# line_sensor.net
KiCad netlist of a schematic drawn in EAGLE
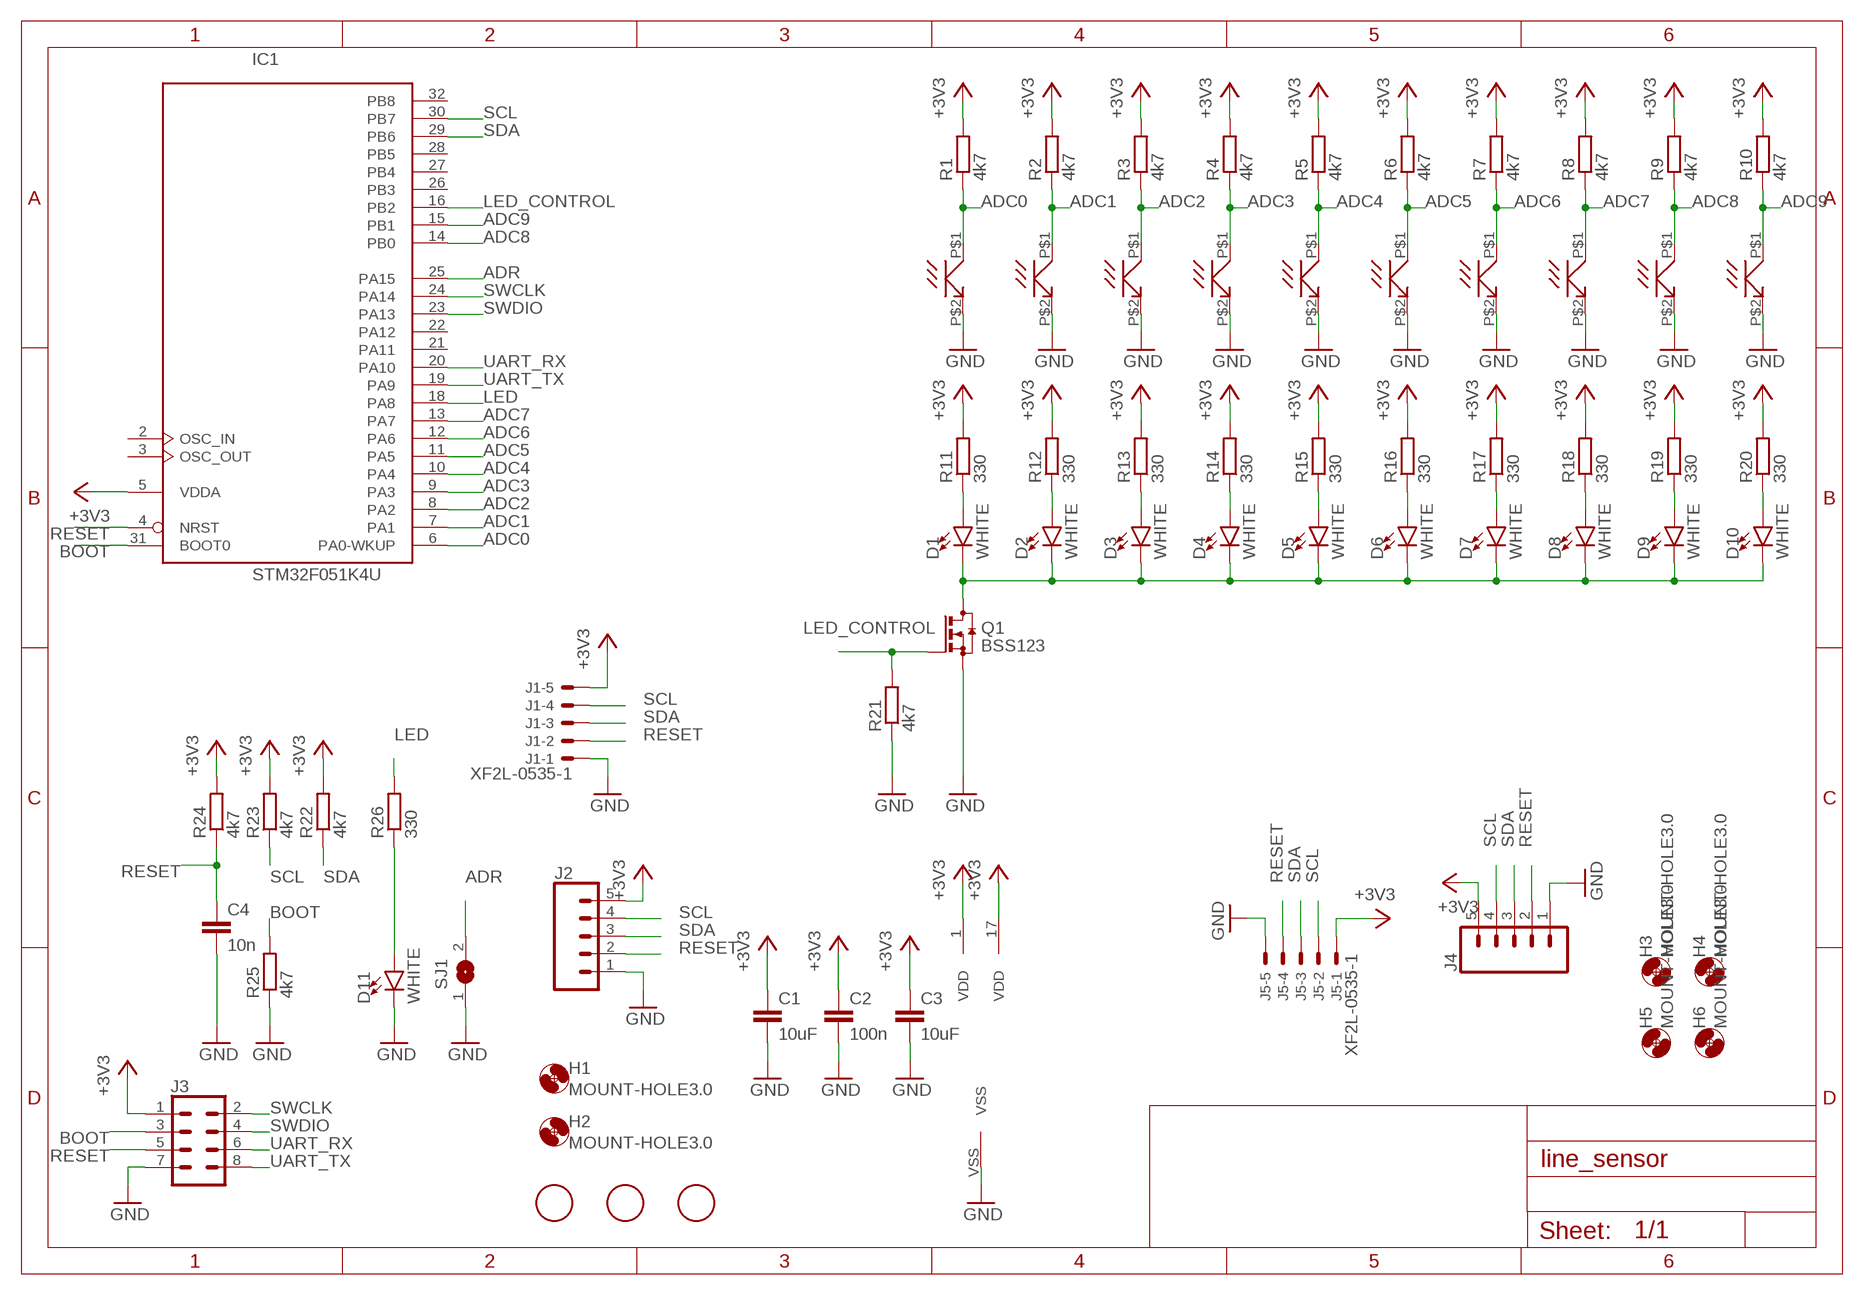
[diagram p0: schematic, sheet 1]

(export (version "E")
  (design (tool "Eeschema 10.0.6"))
  (components
    (comp (ref "C1")
      (value "10uF")
      (footprint "eagle-import:C0805K")
      (libsource (lib "eagle-import") (part "C-EUC0805K"))
    )
    (comp (ref "C2")
      (value "100n")
      (footprint "eagle-import:C0805K")
      (libsource (lib "eagle-import") (part "C-EUC0805K"))
    )
    (comp (ref "C3")
      (value "10uF")
      (footprint "eagle-import:C0805K")
      (libsource (lib "eagle-import") (part "C-EUC0805K"))
    )
    (comp (ref "C4")
      (value "10n")
      (footprint "eagle-import:C0805K")
      (libsource (lib "eagle-import") (part "C-EUC0805K"))
    )
    (comp (ref "D1")
      (value "WHITE")
      (footprint "eagle-import:LED-1206")
      (libsource (lib "eagle-import") (part "LED-WHITE1206"))
    )
    (comp (ref "D2")
      (value "WHITE")
      (footprint "eagle-import:LED-1206")
      (libsource (lib "eagle-import") (part "LED-WHITE1206"))
    )
    (comp (ref "D3")
      (value "WHITE")
      (footprint "eagle-import:LED-1206")
      (libsource (lib "eagle-import") (part "LED-WHITE1206"))
    )
    (comp (ref "D4")
      (value "WHITE")
      (footprint "eagle-import:LED-1206")
      (libsource (lib "eagle-import") (part "LED-WHITE1206"))
    )
    (comp (ref "D5")
      (value "WHITE")
      (footprint "eagle-import:LED-1206")
      (libsource (lib "eagle-import") (part "LED-WHITE1206"))
    )
    (comp (ref "D6")
      (value "WHITE")
      (footprint "eagle-import:LED-1206")
      (libsource (lib "eagle-import") (part "LED-WHITE1206"))
    )
    (comp (ref "D7")
      (value "WHITE")
      (footprint "eagle-import:LED-1206")
      (libsource (lib "eagle-import") (part "LED-WHITE1206"))
    )
    (comp (ref "D8")
      (value "WHITE")
      (footprint "eagle-import:LED-1206")
      (libsource (lib "eagle-import") (part "LED-WHITE1206"))
    )
    (comp (ref "D9")
      (value "WHITE")
      (footprint "eagle-import:LED-1206")
      (libsource (lib "eagle-import") (part "LED-WHITE1206"))
    )
    (comp (ref "D10")
      (value "WHITE")
      (footprint "eagle-import:LED-1206")
      (libsource (lib "eagle-import") (part "LED-WHITE1206"))
    )
    (comp (ref "D11")
      (value "WHITE")
      (footprint "eagle-import:LED-1206")
      (libsource (lib "eagle-import") (part "LED-WHITE1206"))
    )
    (comp (ref "H1")
      (value "MOUNT-HOLE3.0")
      (footprint "eagle-import:3,0")
      (libsource (lib "eagle-import") (part "MOUNT-HOLE3.0"))
    )
    (comp (ref "H2")
      (value "MOUNT-HOLE3.0")
      (footprint "eagle-import:3,0")
      (libsource (lib "eagle-import") (part "MOUNT-HOLE3.0"))
    )
    (comp (ref "H3")
      (value "MOUNT-HOLE3.0")
      (footprint "eagle-import:3,0")
      (libsource (lib "eagle-import") (part "MOUNT-HOLE3.0"))
    )
    (comp (ref "H4")
      (value "MOUNT-HOLE3.0")
      (footprint "eagle-import:3,0")
      (libsource (lib "eagle-import") (part "MOUNT-HOLE3.0"))
    )
    (comp (ref "H5")
      (value "MOUNT-HOLE3.0")
      (footprint "eagle-import:3,0")
      (libsource (lib "eagle-import") (part "MOUNT-HOLE3.0"))
    )
    (comp (ref "H6")
      (value "MOUNT-HOLE3.0")
      (footprint "eagle-import:3,0")
      (libsource (lib "eagle-import") (part "MOUNT-HOLE3.0"))
    )
    (comp (ref "IC1")
      (value "STM32F051K4U")
      (footprint "eagle-import:UFQFPN32")
      (libsource (lib "eagle-import") (part "STM32F051KU4"))
    )
    (comp (ref "J1")
      (value "XF2L-0535-1")
      (footprint "eagle-import:XF2L-0535-1")
      (fields (field (name "MPN") "XF2L-0535-1A"))
      (libsource (lib "eagle-import") (part "XF2-05?35-1L"))
    )
    (comp (ref "J2")
      (value "CONN_05")
      (footprint "eagle-import:1X05")
      (libsource (lib "eagle-import") (part "CONN_05"))
    )
    (comp (ref "J3")
      (value "CONN_04X2")
      (footprint "eagle-import:2X4")
      (libsource (lib "eagle-import") (part "CONN_04X2"))
    )
    (comp (ref "J4")
      (value "CONN_05")
      (footprint "eagle-import:1X05")
      (libsource (lib "eagle-import") (part "CONN_05"))
    )
    (comp (ref "J5")
      (value "XF2L-0535-1")
      (footprint "eagle-import:XF2L-0535-1")
      (fields (field (name "MPN") "XF2L-0535-1A"))
      (libsource (lib "eagle-import") (part "XF2-05?35-1L"))
    )
    (comp (ref "Q1")
      (value "BSS123")
      (footprint "eagle-import:SOT23")
      (libsource (lib "eagle-import") (part "BSS123"))
    )
    (comp (ref "R1")
      (value "4k7")
      (footprint "eagle-import:M0805")
      (libsource (lib "eagle-import") (part "R-EU_M0805"))
    )
    (comp (ref "R2")
      (value "4k7")
      (footprint "eagle-import:M0805")
      (libsource (lib "eagle-import") (part "R-EU_M0805"))
    )
    (comp (ref "R3")
      (value "4k7")
      (footprint "eagle-import:M0805")
      (libsource (lib "eagle-import") (part "R-EU_M0805"))
    )
    (comp (ref "R4")
      (value "4k7")
      (footprint "eagle-import:M0805")
      (libsource (lib "eagle-import") (part "R-EU_M0805"))
    )
    (comp (ref "R5")
      (value "4k7")
      (footprint "eagle-import:M0805")
      (libsource (lib "eagle-import") (part "R-EU_M0805"))
    )
    (comp (ref "R6")
      (value "4k7")
      (footprint "eagle-import:M0805")
      (libsource (lib "eagle-import") (part "R-EU_M0805"))
    )
    (comp (ref "R7")
      (value "4k7")
      (footprint "eagle-import:M0805")
      (libsource (lib "eagle-import") (part "R-EU_M0805"))
    )
    (comp (ref "R8")
      (value "4k7")
      (footprint "eagle-import:M0805")
      (libsource (lib "eagle-import") (part "R-EU_M0805"))
    )
    (comp (ref "R9")
      (value "4k7")
      (footprint "eagle-import:M0805")
      (libsource (lib "eagle-import") (part "R-EU_M0805"))
    )
    (comp (ref "R10")
      (value "4k7")
      (footprint "eagle-import:M0805")
      (libsource (lib "eagle-import") (part "R-EU_M0805"))
    )
    (comp (ref "R11")
      (value "330")
      (footprint "eagle-import:M0805")
      (libsource (lib "eagle-import") (part "R-EU_M0805"))
    )
    (comp (ref "R12")
      (value "330")
      (footprint "eagle-import:M0805")
      (libsource (lib "eagle-import") (part "R-EU_M0805"))
    )
    (comp (ref "R13")
      (value "330")
      (footprint "eagle-import:M0805")
      (libsource (lib "eagle-import") (part "R-EU_M0805"))
    )
    (comp (ref "R14")
      (value "330")
      (footprint "eagle-import:M0805")
      (libsource (lib "eagle-import") (part "R-EU_M0805"))
    )
    (comp (ref "R15")
      (value "330")
      (footprint "eagle-import:M0805")
      (libsource (lib "eagle-import") (part "R-EU_M0805"))
    )
    (comp (ref "R16")
      (value "330")
      (footprint "eagle-import:M0805")
      (libsource (lib "eagle-import") (part "R-EU_M0805"))
    )
    (comp (ref "R17")
      (value "330")
      (footprint "eagle-import:M0805")
      (libsource (lib "eagle-import") (part "R-EU_M0805"))
    )
    (comp (ref "R18")
      (value "330")
      (footprint "eagle-import:M0805")
      (libsource (lib "eagle-import") (part "R-EU_M0805"))
    )
    (comp (ref "R19")
      (value "330")
      (footprint "eagle-import:M0805")
      (libsource (lib "eagle-import") (part "R-EU_M0805"))
    )
    (comp (ref "R20")
      (value "330")
      (footprint "eagle-import:M0805")
      (libsource (lib "eagle-import") (part "R-EU_M0805"))
    )
    (comp (ref "R21")
      (value "4k7")
      (footprint "eagle-import:M0805")
      (libsource (lib "eagle-import") (part "R-EU_M0805"))
    )
    (comp (ref "R22")
      (value "4k7")
      (footprint "eagle-import:M0805")
      (libsource (lib "eagle-import") (part "R-EU_M0805"))
    )
    (comp (ref "R23")
      (value "4k7")
      (footprint "eagle-import:M0805")
      (libsource (lib "eagle-import") (part "R-EU_M0805"))
    )
    (comp (ref "R24")
      (value "4k7")
      (footprint "eagle-import:M0805")
      (libsource (lib "eagle-import") (part "R-EU_M0805"))
    )
    (comp (ref "R25")
      (value "4k7")
      (footprint "eagle-import:M0805")
      (libsource (lib "eagle-import") (part "R-EU_M0805"))
    )
    (comp (ref "R26")
      (value "330")
      (footprint "eagle-import:M0805")
      (libsource (lib "eagle-import") (part "R-EU_M0805"))
    )
    (comp (ref "SJ1") (value "SJ") (footprint "eagle-import:SJ") (libsource (lib "eagle-import") (part "SJ")))
    (comp (ref "U$1")
      (value "SFH3710")
      (footprint "eagle-import:SFH710")
      (libsource (lib "eagle-import") (part "SFH3710"))
    )
    (comp (ref "U$2")
      (value "SFH3710")
      (footprint "eagle-import:SFH710")
      (libsource (lib "eagle-import") (part "SFH3710"))
    )
    (comp (ref "U$3")
      (value "SFH3710")
      (footprint "eagle-import:SFH710")
      (libsource (lib "eagle-import") (part "SFH3710"))
    )
    (comp (ref "U$4")
      (value "SFH3710")
      (footprint "eagle-import:SFH710")
      (libsource (lib "eagle-import") (part "SFH3710"))
    )
    (comp (ref "U$5")
      (value "SFH3710")
      (footprint "eagle-import:SFH710")
      (libsource (lib "eagle-import") (part "SFH3710"))
    )
    (comp (ref "U$6")
      (value "SFH3710")
      (footprint "eagle-import:SFH710")
      (libsource (lib "eagle-import") (part "SFH3710"))
    )
    (comp (ref "U$7")
      (value "SFH3710")
      (footprint "eagle-import:SFH710")
      (libsource (lib "eagle-import") (part "SFH3710"))
    )
    (comp (ref "U$8")
      (value "SFH3710")
      (footprint "eagle-import:SFH710")
      (libsource (lib "eagle-import") (part "SFH3710"))
    )
    (comp (ref "U$9")
      (value "SFH3710")
      (footprint "eagle-import:SFH710")
      (libsource (lib "eagle-import") (part "SFH3710"))
    )
    (comp (ref "U$10")
      (value "SFH3710")
      (footprint "eagle-import:SFH710")
      (libsource (lib "eagle-import") (part "SFH3710"))
    )
    (comp (ref "U$11")
      (value "FIDUCIAL")
      (footprint "eagle-import:FIDUCIAL_1MM")
      (libsource (lib "eagle-import") (part "FIDUCIAL"))
    )
    (comp (ref "U$12")
      (value "FIDUCIAL")
      (footprint "eagle-import:FIDUCIAL_1MM")
      (libsource (lib "eagle-import") (part "FIDUCIAL"))
    )
    (comp (ref "U$13")
      (value "FIDUCIAL")
      (footprint "eagle-import:FIDUCIAL_1MM")
      (libsource (lib "eagle-import") (part "FIDUCIAL"))
    )
  )
  (nets
    (net (code "1") (name "+3V3") (class "Default")
      (node (ref "C1") (pin "1") (pinfunction "1_1") (pintype "passive"))
      (node (ref "C2") (pin "1") (pinfunction "1_1") (pintype "passive"))
      (node (ref "C3") (pin "1") (pinfunction "1_1") (pintype "passive"))
      (node (ref "IC1") (pin "1") (pinfunction "VDD_1") (pintype "power_in"))
      (node (ref "IC1") (pin "17") (pinfunction "VDD_17") (pintype "power_in"))
      (node (ref "IC1") (pin "5") (pinfunction "VDDA_5") (pintype "power_in"))
      (node (ref "J1") (pin "5") (pinfunction "MS_5") (pintype "passive"))
      (node (ref "J2") (pin "5") (pinfunction "5_5") (pintype "passive"))
      (node (ref "J3") (pin "1") (pinfunction "1_1") (pintype "passive"))
      (node (ref "J4") (pin "5") (pinfunction "5_5") (pintype "passive"))
      (node (ref "J5") (pin "1") (pinfunction "MSV_1") (pintype "passive"))
      (node (ref "R1") (pin "2") (pinfunction "2_2") (pintype "passive"))
      (node (ref "R10") (pin "2") (pinfunction "2_2") (pintype "passive"))
      (node (ref "R11") (pin "2") (pinfunction "2_2") (pintype "passive"))
      (node (ref "R12") (pin "2") (pinfunction "2_2") (pintype "passive"))
      (node (ref "R13") (pin "2") (pinfunction "2_2") (pintype "passive"))
      (node (ref "R14") (pin "2") (pinfunction "2_2") (pintype "passive"))
      (node (ref "R15") (pin "2") (pinfunction "2_2") (pintype "passive"))
      (node (ref "R16") (pin "2") (pinfunction "2_2") (pintype "passive"))
      (node (ref "R17") (pin "2") (pinfunction "2_2") (pintype "passive"))
      (node (ref "R18") (pin "2") (pinfunction "2_2") (pintype "passive"))
      (node (ref "R19") (pin "2") (pinfunction "2_2") (pintype "passive"))
      (node (ref "R2") (pin "2") (pinfunction "2_2") (pintype "passive"))
      (node (ref "R20") (pin "2") (pinfunction "2_2") (pintype "passive"))
      (node (ref "R22") (pin "2") (pinfunction "2_2") (pintype "passive"))
      (node (ref "R23") (pin "2") (pinfunction "2_2") (pintype "passive"))
      (node (ref "R24") (pin "2") (pinfunction "2_2") (pintype "passive"))
      (node (ref "R3") (pin "2") (pinfunction "2_2") (pintype "passive"))
      (node (ref "R4") (pin "2") (pinfunction "2_2") (pintype "passive"))
      (node (ref "R5") (pin "2") (pinfunction "2_2") (pintype "passive"))
      (node (ref "R6") (pin "2") (pinfunction "2_2") (pintype "passive"))
      (node (ref "R7") (pin "2") (pinfunction "2_2") (pintype "passive"))
      (node (ref "R8") (pin "2") (pinfunction "2_2") (pintype "passive"))
      (node (ref "R9") (pin "2") (pinfunction "2_2") (pintype "passive"))
    )
    (net (code "2") (name "/ADC0") (class "Default")
      (node (ref "IC1") (pin "6") (pinfunction "PA0-WKUP_6") (pintype "bidirectional"))
      (node (ref "R1") (pin "1") (pinfunction "1_1") (pintype "passive"))
      (node (ref "U$1") (pin "P$1") (pinfunction "C_P$1") (pintype "bidirectional"))
    )
    (net (code "3") (name "/ADC1") (class "Default")
      (node (ref "IC1") (pin "7") (pinfunction "PA1_7") (pintype "bidirectional"))
      (node (ref "R2") (pin "1") (pinfunction "1_1") (pintype "passive"))
      (node (ref "U$2") (pin "P$1") (pinfunction "C_P$1") (pintype "bidirectional"))
    )
    (net (code "4") (name "/ADC2") (class "Default")
      (node (ref "IC1") (pin "8") (pinfunction "PA2_8") (pintype "bidirectional"))
      (node (ref "R3") (pin "1") (pinfunction "1_1") (pintype "passive"))
      (node (ref "U$3") (pin "P$1") (pinfunction "C_P$1") (pintype "bidirectional"))
    )
    (net (code "5") (name "/ADC3") (class "Default")
      (node (ref "IC1") (pin "9") (pinfunction "PA3_9") (pintype "bidirectional"))
      (node (ref "R4") (pin "1") (pinfunction "1_1") (pintype "passive"))
      (node (ref "U$4") (pin "P$1") (pinfunction "C_P$1") (pintype "bidirectional"))
    )
    (net (code "6") (name "/ADC4") (class "Default")
      (node (ref "IC1") (pin "10") (pinfunction "PA4_10") (pintype "bidirectional"))
      (node (ref "R5") (pin "1") (pinfunction "1_1") (pintype "passive"))
      (node (ref "U$5") (pin "P$1") (pinfunction "C_P$1") (pintype "bidirectional"))
    )
    (net (code "7") (name "/ADC5") (class "Default")
      (node (ref "IC1") (pin "11") (pinfunction "PA5_11") (pintype "bidirectional"))
      (node (ref "R6") (pin "1") (pinfunction "1_1") (pintype "passive"))
      (node (ref "U$6") (pin "P$1") (pinfunction "C_P$1") (pintype "bidirectional"))
    )
    (net (code "8") (name "/ADC6") (class "Default")
      (node (ref "IC1") (pin "12") (pinfunction "PA6_12") (pintype "bidirectional"))
      (node (ref "R7") (pin "1") (pinfunction "1_1") (pintype "passive"))
      (node (ref "U$7") (pin "P$1") (pinfunction "C_P$1") (pintype "bidirectional"))
    )
    (net (code "9") (name "/ADC7") (class "Default")
      (node (ref "IC1") (pin "13") (pinfunction "PA7_13") (pintype "bidirectional"))
      (node (ref "R8") (pin "1") (pinfunction "1_1") (pintype "passive"))
      (node (ref "U$8") (pin "P$1") (pinfunction "C_P$1") (pintype "bidirectional"))
    )
    (net (code "10") (name "/ADC8") (class "Default")
      (node (ref "IC1") (pin "14") (pinfunction "PB0_14") (pintype "bidirectional"))
      (node (ref "R9") (pin "1") (pinfunction "1_1") (pintype "passive"))
      (node (ref "U$9") (pin "P$1") (pinfunction "C_P$1") (pintype "bidirectional"))
    )
    (net (code "11") (name "/ADC9") (class "Default")
      (node (ref "IC1") (pin "15") (pinfunction "PB1_15") (pintype "bidirectional"))
      (node (ref "R10") (pin "1") (pinfunction "1_1") (pintype "passive"))
      (node (ref "U$10") (pin "P$1") (pinfunction "C_P$1") (pintype "bidirectional"))
    )
    (net (code "12") (name "/ADR") (class "Default")
      (node (ref "IC1") (pin "25") (pinfunction "PA15_25") (pintype "bidirectional"))
      (node (ref "SJ1") (pin "2") (pinfunction "2_2") (pintype "passive"))
    )
    (net (code "13") (name "/BOOT") (class "Default")
      (node (ref "IC1") (pin "31") (pinfunction "BOOT0_31") (pintype "input"))
      (node (ref "J3") (pin "3") (pinfunction "3_3") (pintype "passive"))
      (node (ref "R25") (pin "2") (pinfunction "2_2") (pintype "passive"))
    )
    (net (code "14") (name "/LED") (class "Default")
      (node (ref "IC1") (pin "18") (pinfunction "PA8_18") (pintype "bidirectional"))
      (node (ref "R26") (pin "2") (pinfunction "2_2") (pintype "passive"))
    )
    (net (code "15") (name "/LED_CONTROL") (class "Default")
      (node (ref "IC1") (pin "16") (pinfunction "PB2_16") (pintype "bidirectional"))
      (node (ref "Q1") (pin "1") (pinfunction "G_1") (pintype "passive"))
      (node (ref "R21") (pin "2") (pinfunction "2_2") (pintype "passive"))
    )
    (net (code "16") (name "/RESET") (class "Default")
      (node (ref "C4") (pin "1") (pinfunction "1_1") (pintype "passive"))
      (node (ref "IC1") (pin "4") (pinfunction "NRST_4") (pintype "bidirectional"))
      (node (ref "J1") (pin "2") (pinfunction "MS_2") (pintype "passive"))
      (node (ref "J2") (pin "2") (pinfunction "2_2") (pintype "passive"))
      (node (ref "J3") (pin "5") (pinfunction "5_5") (pintype "passive"))
      (node (ref "J4") (pin "2") (pinfunction "2_2") (pintype "passive"))
      (node (ref "J5") (pin "4") (pinfunction "MS_4") (pintype "passive"))
      (node (ref "R24") (pin "1") (pinfunction "1_1") (pintype "passive"))
    )
    (net (code "17") (name "/SCL") (class "Default")
      (node (ref "IC1") (pin "30") (pinfunction "PB7_30") (pintype "bidirectional"))
      (node (ref "J1") (pin "4") (pinfunction "MS_4") (pintype "passive"))
      (node (ref "J2") (pin "4") (pinfunction "4_4") (pintype "passive"))
      (node (ref "J4") (pin "4") (pinfunction "4_4") (pintype "passive"))
      (node (ref "J5") (pin "2") (pinfunction "MS_2") (pintype "passive"))
      (node (ref "R23") (pin "1") (pinfunction "1_1") (pintype "passive"))
    )
    (net (code "18") (name "/SDA") (class "Default")
      (node (ref "IC1") (pin "29") (pinfunction "PB6_29") (pintype "bidirectional"))
      (node (ref "J1") (pin "3") (pinfunction "MS_3") (pintype "passive"))
      (node (ref "J2") (pin "3") (pinfunction "3_3") (pintype "passive"))
      (node (ref "J4") (pin "3") (pinfunction "3_3") (pintype "passive"))
      (node (ref "J5") (pin "3") (pinfunction "MS_3") (pintype "passive"))
      (node (ref "R22") (pin "1") (pinfunction "1_1") (pintype "passive"))
    )
    (net (code "19") (name "/SWCLK") (class "Default")
      (node (ref "IC1") (pin "24") (pinfunction "PA14_24") (pintype "bidirectional"))
      (node (ref "J3") (pin "2") (pinfunction "2_2") (pintype "passive"))
    )
    (net (code "20") (name "/SWDIO") (class "Default")
      (node (ref "IC1") (pin "23") (pinfunction "PA13_23") (pintype "bidirectional"))
      (node (ref "J3") (pin "4") (pinfunction "4_4") (pintype "passive"))
    )
    (net (code "21") (name "/UART_RX") (class "Default")
      (node (ref "IC1") (pin "20") (pinfunction "PA10_20") (pintype "bidirectional"))
      (node (ref "J3") (pin "6") (pinfunction "6_6") (pintype "passive"))
    )
    (net (code "22") (name "/UART_TX") (class "Default")
      (node (ref "IC1") (pin "19") (pinfunction "PA9_19") (pintype "bidirectional"))
      (node (ref "J3") (pin "8") (pinfunction "8_8") (pintype "passive"))
    )
    (net (code "23") (name "GND") (class "Default")
      (node (ref "C1") (pin "2") (pinfunction "2_2") (pintype "passive"))
      (node (ref "C2") (pin "2") (pinfunction "2_2") (pintype "passive"))
      (node (ref "C3") (pin "2") (pinfunction "2_2") (pintype "passive"))
      (node (ref "C4") (pin "2") (pinfunction "2_2") (pintype "passive"))
      (node (ref "D11") (pin "C") (pinfunction "C_C") (pintype "passive"))
      (node (ref "IC1") (pin "VSS") (pinfunction "VSS_VSS") (pintype "power_in"))
      (node (ref "J1") (pin "1") (pinfunction "MSV_1") (pintype "passive"))
      (node (ref "J2") (pin "1") (pinfunction "1_1") (pintype "passive"))
      (node (ref "J3") (pin "7") (pinfunction "7_7") (pintype "passive"))
      (node (ref "J4") (pin "1") (pinfunction "1_1") (pintype "passive"))
      (node (ref "J5") (pin "5") (pinfunction "MS_5") (pintype "passive"))
      (node (ref "Q1") (pin "2") (pinfunction "S_2") (pintype "passive"))
      (node (ref "R21") (pin "1") (pinfunction "1_1") (pintype "passive"))
      (node (ref "R25") (pin "1") (pinfunction "1_1") (pintype "passive"))
      (node (ref "SJ1") (pin "1") (pinfunction "1_1") (pintype "passive"))
      (node (ref "U$1") (pin "P$2") (pinfunction "E_P$2") (pintype "bidirectional"))
      (node (ref "U$10") (pin "P$2") (pinfunction "E_P$2") (pintype "bidirectional"))
      (node (ref "U$2") (pin "P$2") (pinfunction "E_P$2") (pintype "bidirectional"))
      (node (ref "U$3") (pin "P$2") (pinfunction "E_P$2") (pintype "bidirectional"))
      (node (ref "U$4") (pin "P$2") (pinfunction "E_P$2") (pintype "bidirectional"))
      (node (ref "U$5") (pin "P$2") (pinfunction "E_P$2") (pintype "bidirectional"))
      (node (ref "U$6") (pin "P$2") (pinfunction "E_P$2") (pintype "bidirectional"))
      (node (ref "U$7") (pin "P$2") (pinfunction "E_P$2") (pintype "bidirectional"))
      (node (ref "U$8") (pin "P$2") (pinfunction "E_P$2") (pintype "bidirectional"))
      (node (ref "U$9") (pin "P$2") (pinfunction "E_P$2") (pintype "bidirectional"))
    )
    (net (code "24") (name "Net-(D1-PadA)") (class "Default")
      (node (ref "D1") (pin "A") (pinfunction "A_A") (pintype "passive"))
      (node (ref "R11") (pin "1") (pinfunction "1_1") (pintype "passive"))
    )
    (net (code "25") (name "Net-(D2-PadA)") (class "Default")
      (node (ref "D2") (pin "A") (pinfunction "A_A") (pintype "passive"))
      (node (ref "R12") (pin "1") (pinfunction "1_1") (pintype "passive"))
    )
    (net (code "26") (name "Net-(D3-PadA)") (class "Default")
      (node (ref "D3") (pin "A") (pinfunction "A_A") (pintype "passive"))
      (node (ref "R13") (pin "1") (pinfunction "1_1") (pintype "passive"))
    )
    (net (code "27") (name "Net-(D4-PadA)") (class "Default")
      (node (ref "D4") (pin "A") (pinfunction "A_A") (pintype "passive"))
      (node (ref "R14") (pin "1") (pinfunction "1_1") (pintype "passive"))
    )
    (net (code "28") (name "Net-(D5-PadA)") (class "Default")
      (node (ref "D5") (pin "A") (pinfunction "A_A") (pintype "passive"))
      (node (ref "R15") (pin "1") (pinfunction "1_1") (pintype "passive"))
    )
    (net (code "29") (name "Net-(D6-PadA)") (class "Default")
      (node (ref "D6") (pin "A") (pinfunction "A_A") (pintype "passive"))
      (node (ref "R16") (pin "1") (pinfunction "1_1") (pintype "passive"))
    )
    (net (code "30") (name "Net-(D7-PadA)") (class "Default")
      (node (ref "D7") (pin "A") (pinfunction "A_A") (pintype "passive"))
      (node (ref "R17") (pin "1") (pinfunction "1_1") (pintype "passive"))
    )
    (net (code "31") (name "Net-(D8-PadA)") (class "Default")
      (node (ref "D8") (pin "A") (pinfunction "A_A") (pintype "passive"))
      (node (ref "R18") (pin "1") (pinfunction "1_1") (pintype "passive"))
    )
    (net (code "32") (name "Net-(D9-PadA)") (class "Default")
      (node (ref "D9") (pin "A") (pinfunction "A_A") (pintype "passive"))
      (node (ref "R19") (pin "1") (pinfunction "1_1") (pintype "passive"))
    )
    (net (code "33") (name "Net-(D10-PadA)") (class "Default")
      (node (ref "D10") (pin "A") (pinfunction "A_A") (pintype "passive"))
      (node (ref "R20") (pin "1") (pinfunction "1_1") (pintype "passive"))
    )
    (net (code "34") (name "Net-(D11-PadA)") (class "Default")
      (node (ref "D11") (pin "A") (pinfunction "A_A") (pintype "passive"))
      (node (ref "R26") (pin "1") (pinfunction "1_1") (pintype "passive"))
    )
    (net (code "35") (name "Net-(Q1-D)") (class "Default")
      (node (ref "D1") (pin "C") (pinfunction "C_C") (pintype "passive"))
      (node (ref "D10") (pin "C") (pinfunction "C_C") (pintype "passive"))
      (node (ref "D2") (pin "C") (pinfunction "C_C") (pintype "passive"))
      (node (ref "D3") (pin "C") (pinfunction "C_C") (pintype "passive"))
      (node (ref "D4") (pin "C") (pinfunction "C_C") (pintype "passive"))
      (node (ref "D5") (pin "C") (pinfunction "C_C") (pintype "passive"))
      (node (ref "D6") (pin "C") (pinfunction "C_C") (pintype "passive"))
      (node (ref "D7") (pin "C") (pinfunction "C_C") (pintype "passive"))
      (node (ref "D8") (pin "C") (pinfunction "C_C") (pintype "passive"))
      (node (ref "D9") (pin "C") (pinfunction "C_C") (pintype "passive"))
      (node (ref "Q1") (pin "3") (pinfunction "D_3") (pintype "passive"))
    )
    (net (code "36") (name "unconnected-(IC1A-OSC_IN-Pad2)") (class "Default")
      (node (ref "IC1") (pin "2") (pinfunction "OSC_IN_2") (pintype "bidirectional"))
    )
    (net (code "37") (name "unconnected-(IC1A-OSC_OUT-Pad3)") (class "Default")
      (node (ref "IC1") (pin "3") (pinfunction "OSC_OUT_3") (pintype "bidirectional"))
    )
    (net (code "38") (name "unconnected-(IC1A-PA11-Pad21)") (class "Default")
      (node (ref "IC1") (pin "21") (pinfunction "PA11_21") (pintype "bidirectional"))
    )
    (net (code "39") (name "unconnected-(IC1A-PA12-Pad22)") (class "Default")
      (node (ref "IC1") (pin "22") (pinfunction "PA12_22") (pintype "bidirectional"))
    )
    (net (code "40") (name "unconnected-(IC1A-PB3-Pad26)") (class "Default")
      (node (ref "IC1") (pin "26") (pinfunction "PB3_26") (pintype "bidirectional"))
    )
    (net (code "41") (name "unconnected-(IC1A-PB4-Pad27)") (class "Default")
      (node (ref "IC1") (pin "27") (pinfunction "PB4_27") (pintype "bidirectional"))
    )
    (net (code "42") (name "unconnected-(IC1A-PB5-Pad28)") (class "Default")
      (node (ref "IC1") (pin "28") (pinfunction "PB5_28") (pintype "bidirectional"))
    )
    (net (code "43") (name "unconnected-(IC1A-PB8-Pad32)") (class "Default")
      (node (ref "IC1") (pin "32") (pinfunction "PB8_32") (pintype "bidirectional"))
    )
  )
)
